# SECUREBRD_001.net
KiCad netlist of a schematic drawn in EAGLE
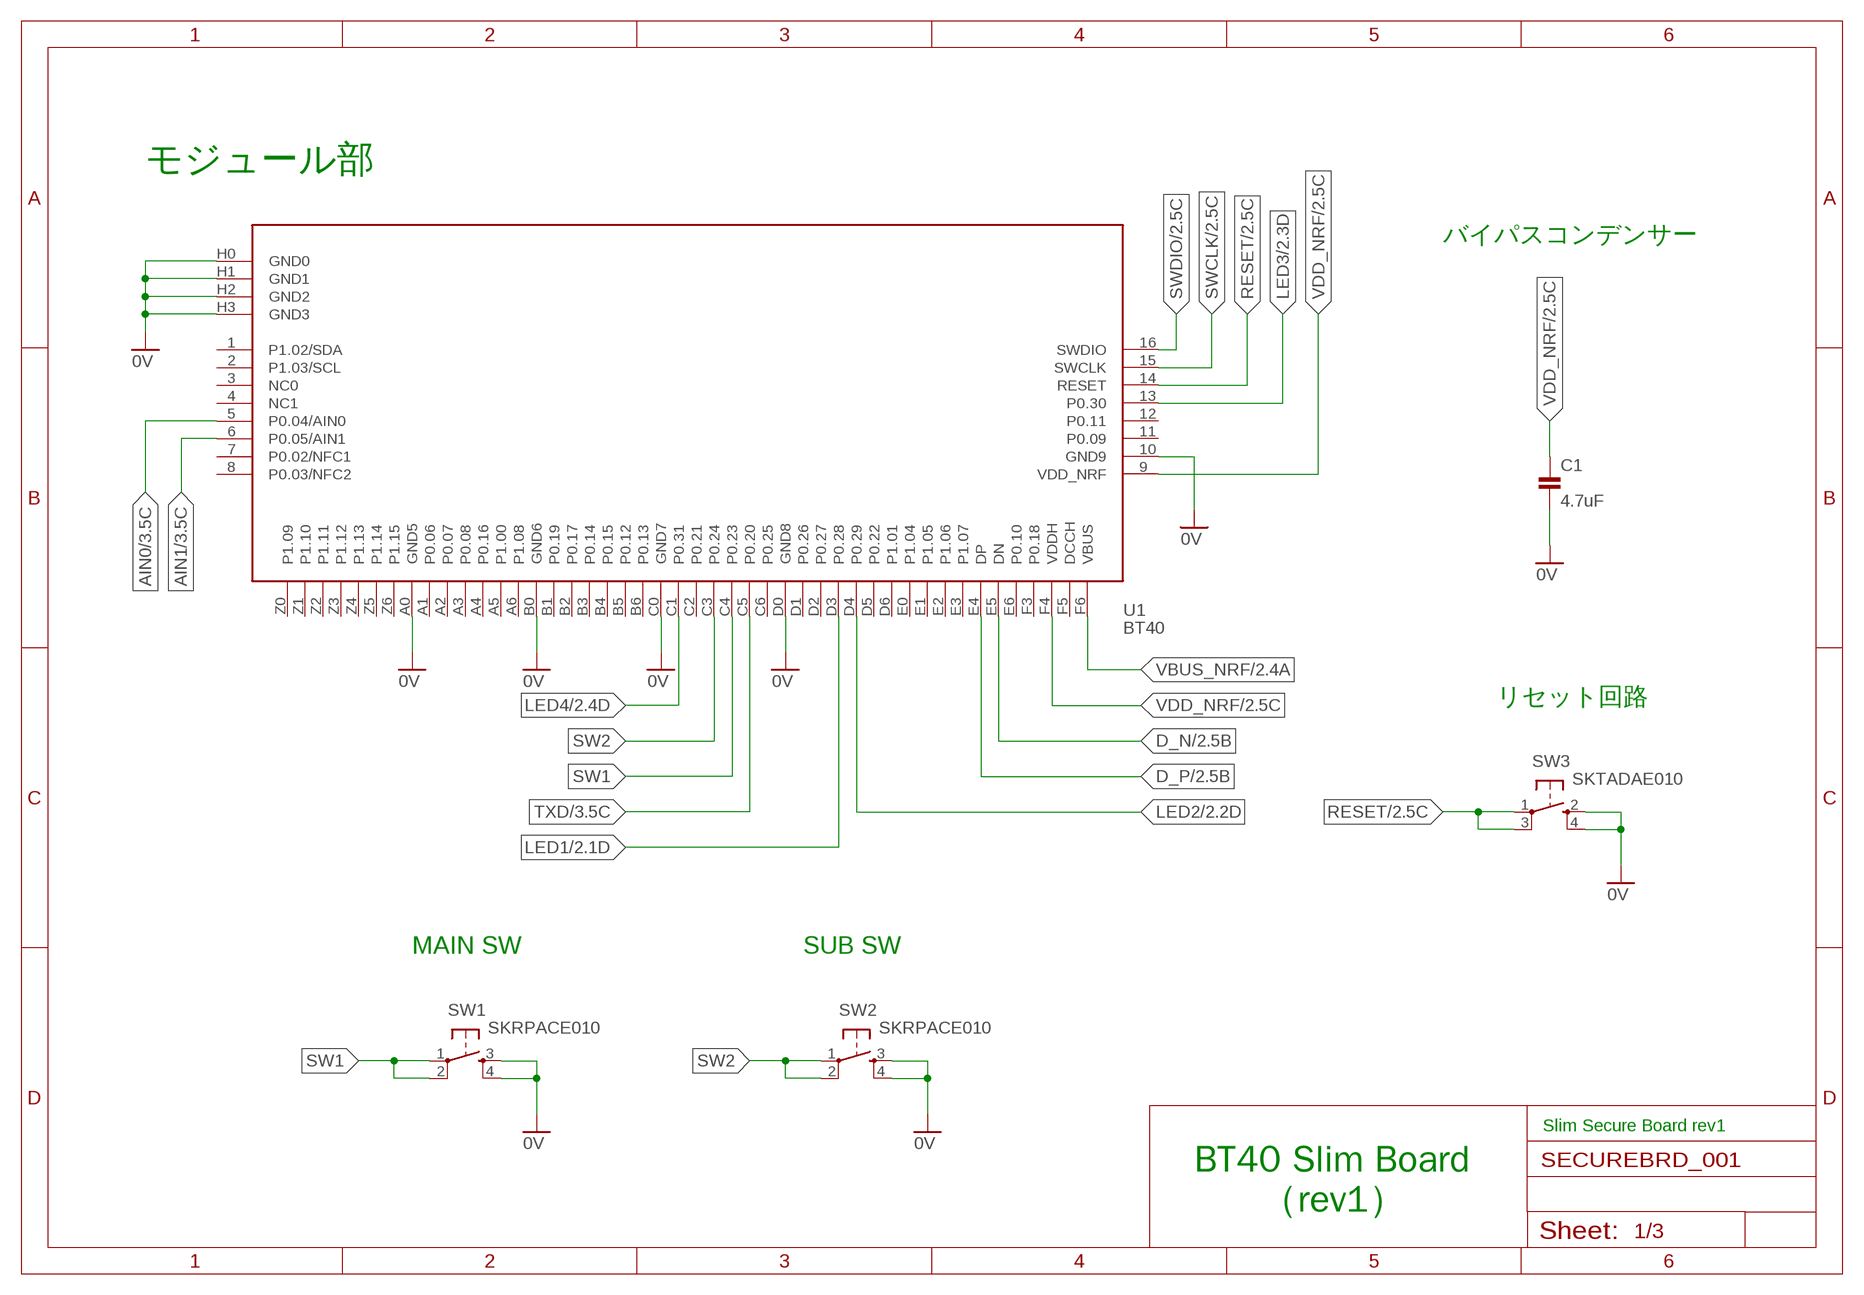
[diagram p0: schematic, sheet 1]
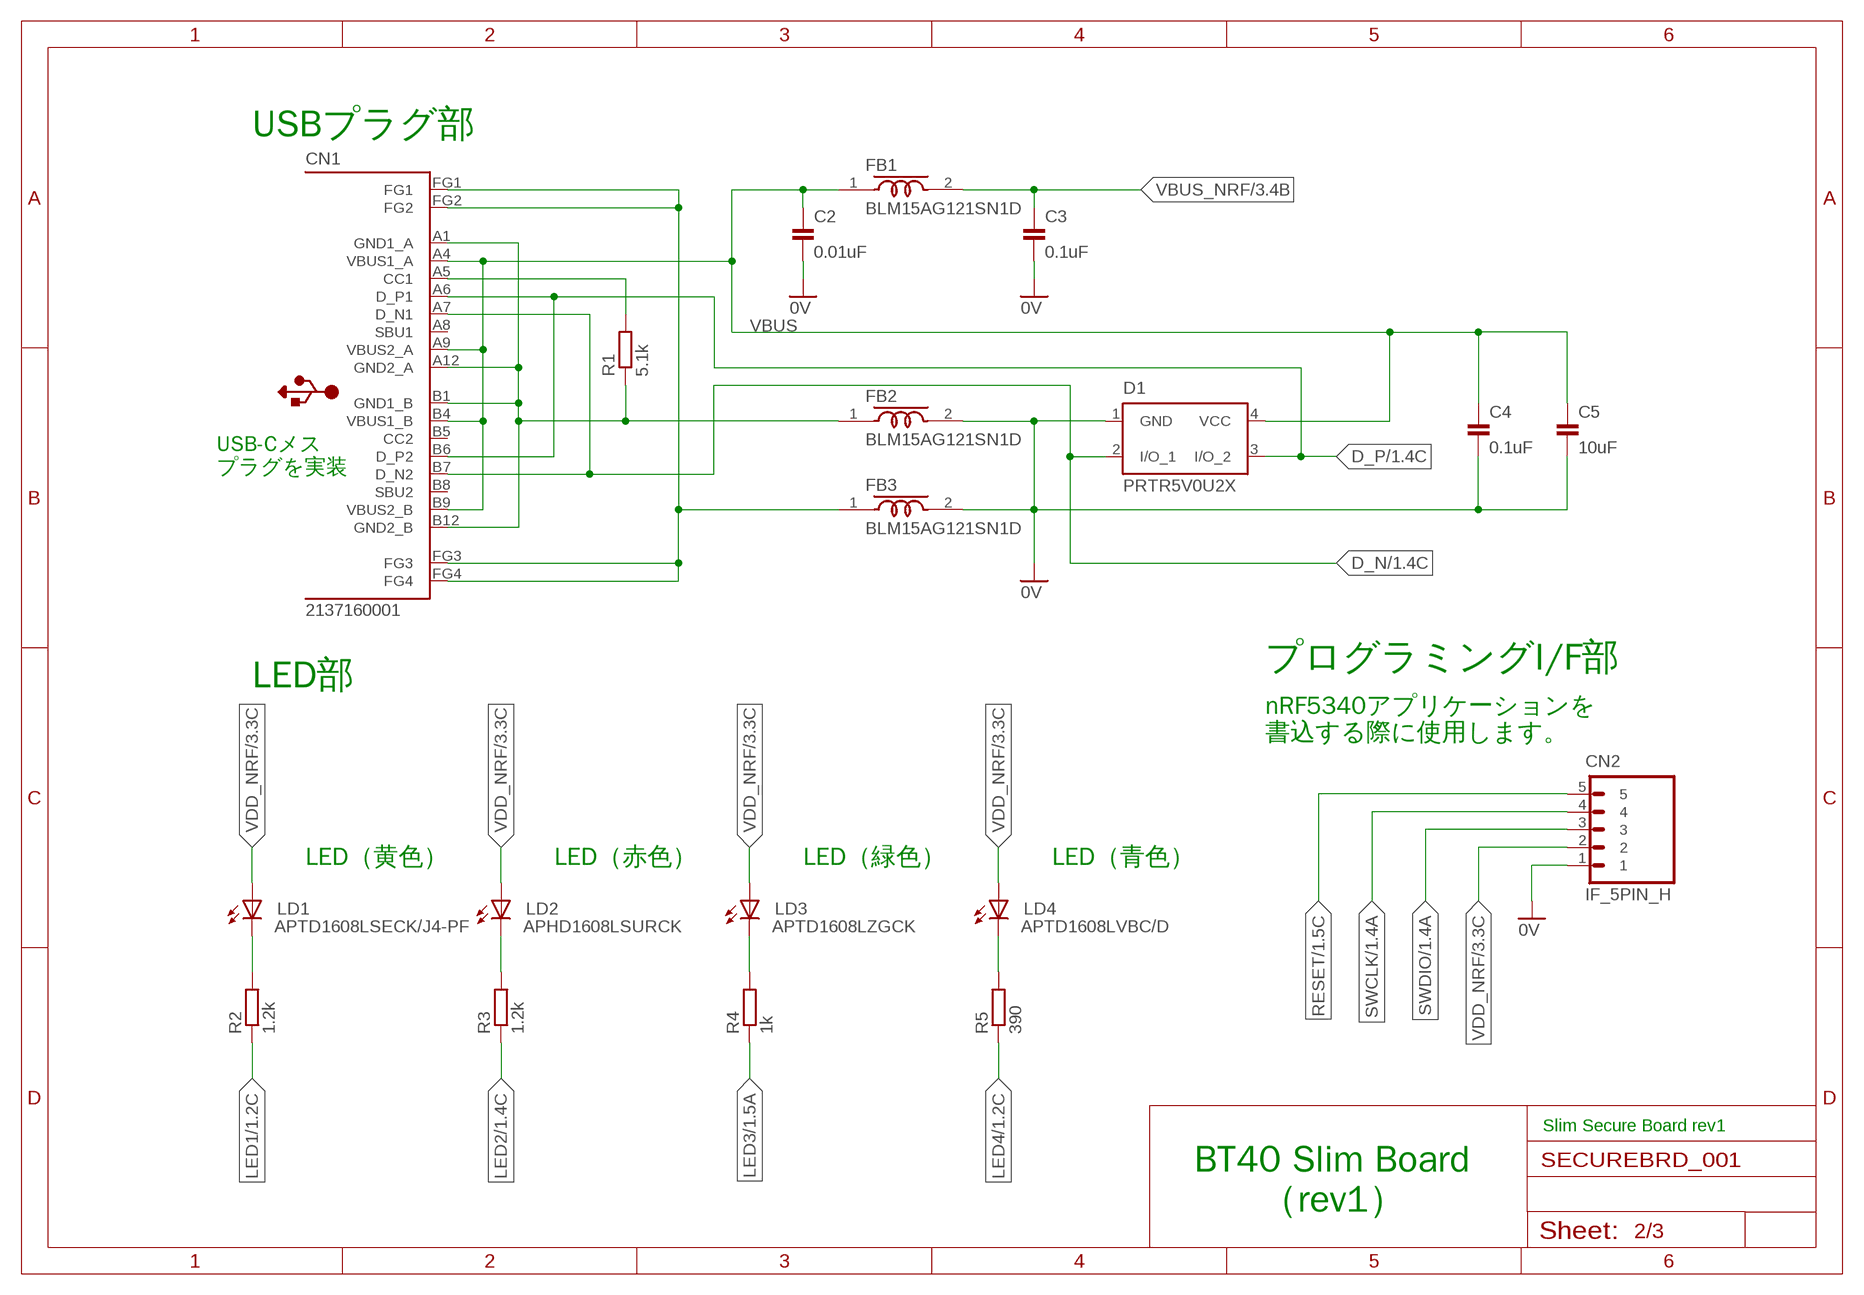
[diagram p1: schematic, sheet 2]
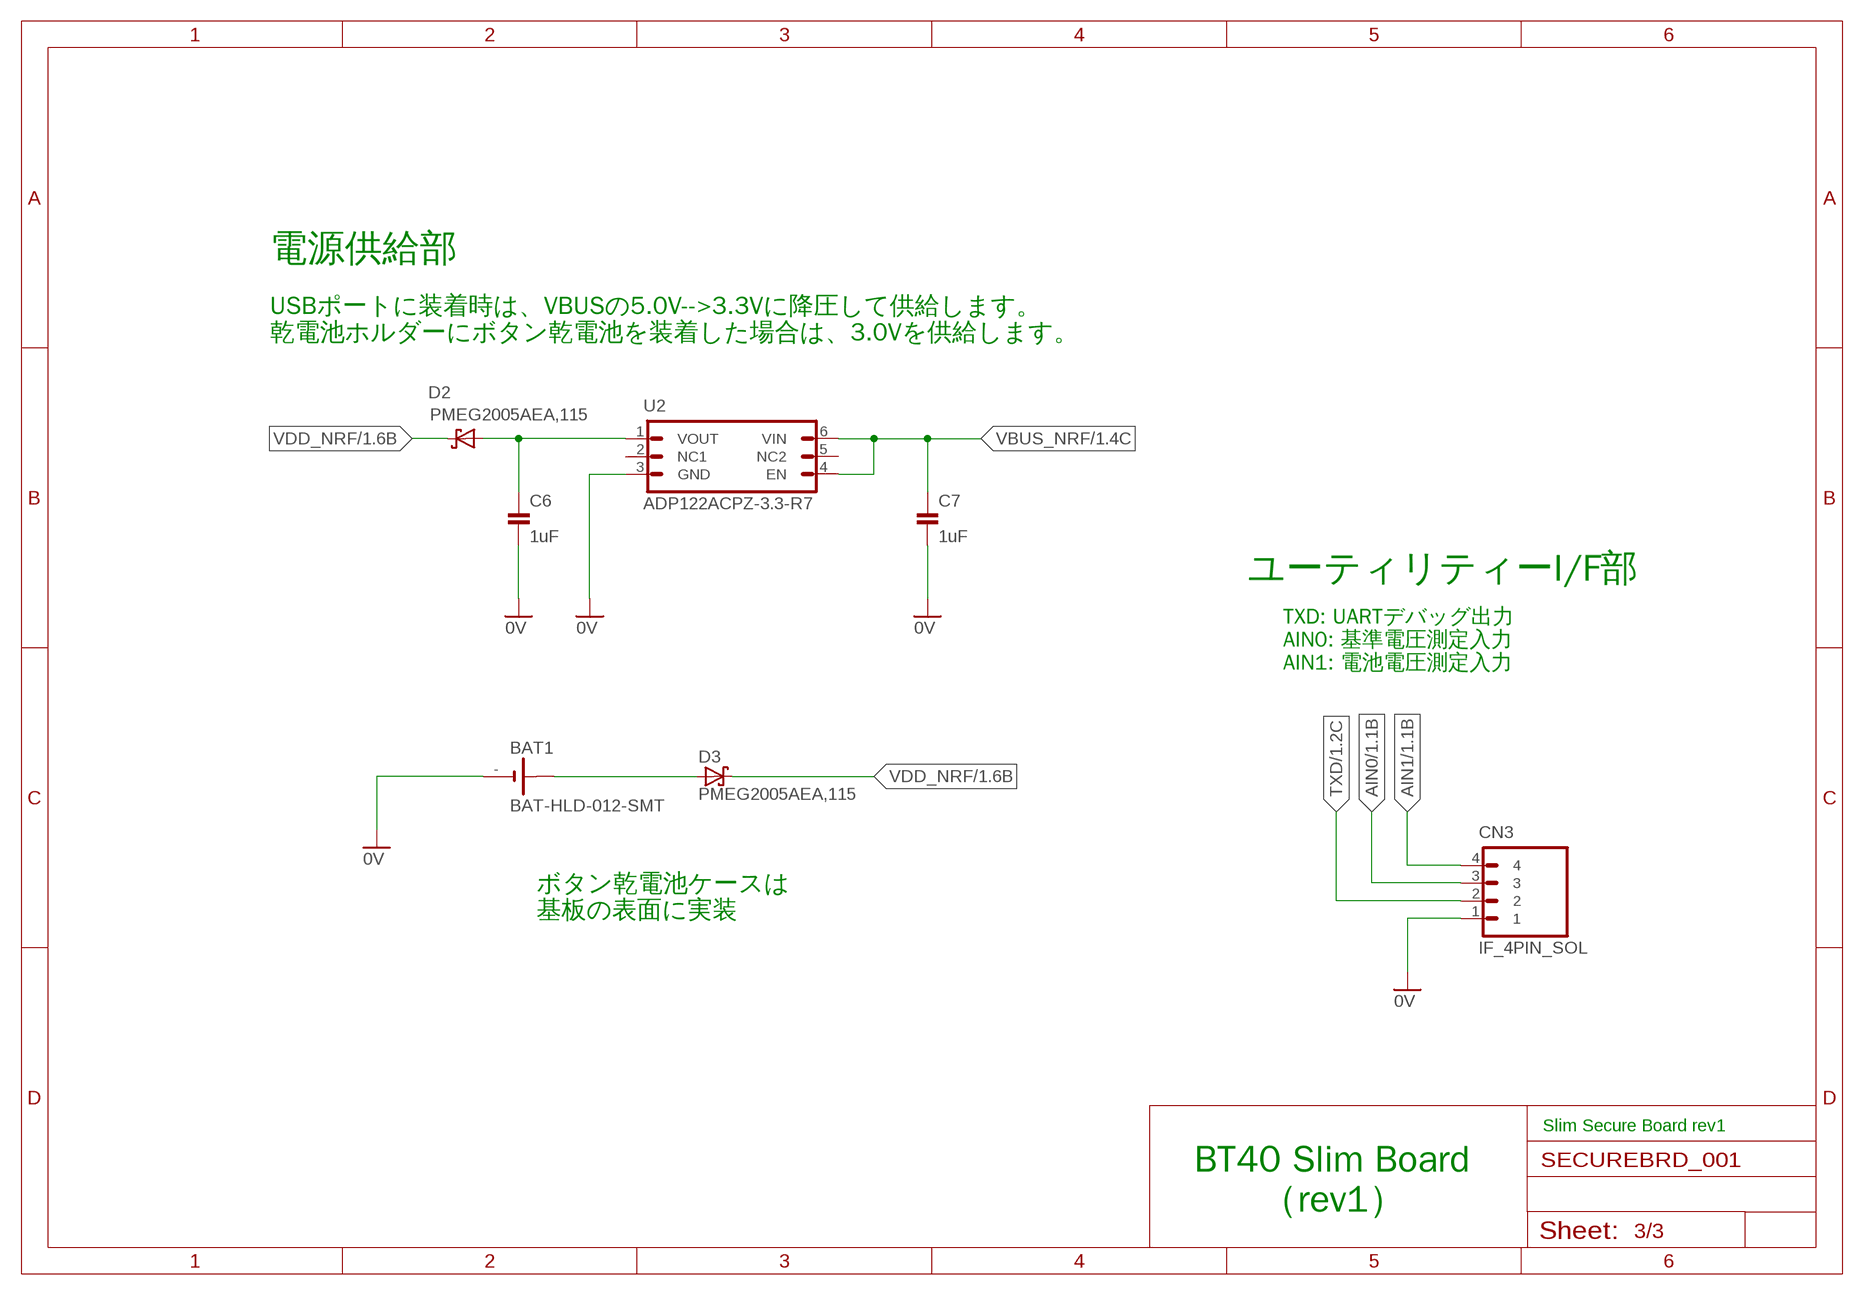
[diagram p2: schematic, sheet 3]

(export (version "E")
  (design (tool "Eeschema 10.0.6"))
  (components
    (comp (ref "C1")
      (value "4.7uF")
      (footprint "eagle-import:C0603K")
      (libsource (lib "eagle-import") (part "CAP_0603"))
    )
    (comp (ref "SW1")
      (value "SKRPACE010")
      (footprint "eagle-import:SKRPACE010")
      (libsource (lib "eagle-import") (part "SKRPACE010"))
    )
    (comp (ref "SW2")
      (value "SKRPACE010")
      (footprint "eagle-import:SKRPACE010")
      (libsource (lib "eagle-import") (part "SKRPACE010"))
    )
    (comp (ref "SW3")
      (value "SKTADAE010")
      (footprint "eagle-import:SKTADAE010")
      (libsource (lib "eagle-import") (part "SKTADAE010"))
    )
    (comp (ref "U1")
      (value "BT40")
      (footprint "eagle-import:BM40-B_1PRIMARY")
      (libsource (lib "eagle-import") (part "BT40"))
    )
    (comp (ref "BAT1")
      (value "BAT-HLD-012-SMT")
      (footprint "eagle-import:BAT-HLD-012-SMT")
      (libsource (lib "eagle-import") (part "BAT-HLD-012-SMT"))
    )
    (comp (ref "C6")
      (value "1uF")
      (footprint "eagle-import:C0603K")
      (libsource (lib "eagle-import") (part "CAP_0603"))
    )
    (comp (ref "C7")
      (value "1uF")
      (footprint "eagle-import:C0603K")
      (libsource (lib "eagle-import") (part "CAP_0603"))
    )
    (comp (ref "CN3")
      (value "IF_4PIN_SOL")
      (footprint "eagle-import:SOLPAD_4PIN")
      (libsource (lib "eagle-import") (part "IF_4PIN_SOL"))
    )
    (comp (ref "D2")
      (value "PMEG2005AEA,115")
      (footprint "eagle-import:SOD323-W")
      (libsource (lib "eagle-import") (part "PMEG2005AEA,115"))
    )
    (comp (ref "D3")
      (value "PMEG2005AEA,115")
      (footprint "eagle-import:SOD323-W")
      (libsource (lib "eagle-import") (part "PMEG2005AEA,115"))
    )
    (comp (ref "U2")
      (value "ADP122ACPZ-3.3-R7")
      (footprint "eagle-import:6-LFCSP_UD")
      (libsource (lib "eagle-import") (part "ADP122ACPZ-3.3-R7"))
    )
    (comp (ref "C2")
      (value "0.01uF")
      (footprint "eagle-import:C0402K")
      (libsource (lib "eagle-import") (part "CAP_0402K"))
    )
    (comp (ref "C3")
      (value "0.1uF")
      (footprint "eagle-import:C0402K")
      (libsource (lib "eagle-import") (part "CAP_0402K"))
    )
    (comp (ref "C4")
      (value "0.1uF")
      (footprint "eagle-import:C0402K")
      (libsource (lib "eagle-import") (part "CAP_0402K"))
    )
    (comp (ref "C5")
      (value "10uF")
      (footprint "eagle-import:C0603K")
      (libsource (lib "eagle-import") (part "CAP_0603"))
    )
    (comp (ref "CN1")
      (value "2137160001")
      (footprint "eagle-import:2137160001")
      (libsource (lib "eagle-import") (part "2137160001"))
    )
    (comp (ref "CN2")
      (value "IF_5PIN_H")
      (footprint "eagle-import:HEADER_5PIN")
      (libsource (lib "eagle-import") (part "IF_5PIN_H"))
    )
    (comp (ref "D1")
      (value "PRTR5V0U2X")
      (footprint "eagle-import:SOT143B")
      (libsource (lib "eagle-import") (part "PRTR5V0U2X"))
    )
    (comp (ref "FB1")
      (value "BLM15AG121SN1D")
      (footprint "eagle-import:C0402K")
      (libsource (lib "eagle-import") (part "BLM15AG121SN1D"))
    )
    (comp (ref "FB2")
      (value "BLM15AG121SN1D")
      (footprint "eagle-import:C0402K")
      (libsource (lib "eagle-import") (part "BLM15AG121SN1D"))
    )
    (comp (ref "FB3")
      (value "BLM15AG121SN1D")
      (footprint "eagle-import:C0402K")
      (libsource (lib "eagle-import") (part "BLM15AG121SN1D"))
    )
    (comp (ref "LD1")
      (value "APTD1608LSECK/J4-PF")
      (footprint "eagle-import:APTD1608")
      (libsource (lib "eagle-import") (part "APTD1608LSECK/J4-PF"))
    )
    (comp (ref "LD2")
      (value "APHD1608LSURCK")
      (footprint "eagle-import:APTD1608")
      (libsource (lib "eagle-import") (part "APHD1608LSURCK"))
    )
    (comp (ref "LD3")
      (value "APTD1608LZGCK")
      (footprint "eagle-import:APTD1608")
      (libsource (lib "eagle-import") (part "APTD1608LZGCK"))
    )
    (comp (ref "LD4")
      (value "APTD1608LVBC/D")
      (footprint "eagle-import:APTD1608")
      (libsource (lib "eagle-import") (part "APTD1608LVBC/D"))
    )
    (comp (ref "R1")
      (value "5.1k")
      (footprint "eagle-import:R0402")
      (libsource (lib "eagle-import") (part "RESISTOR_0402"))
    )
    (comp (ref "R2")
      (value "1.2k")
      (footprint "eagle-import:R0402")
      (libsource (lib "eagle-import") (part "RESISTOR_0402"))
    )
    (comp (ref "R3")
      (value "1.2k")
      (footprint "eagle-import:R0402")
      (libsource (lib "eagle-import") (part "RESISTOR_0402"))
    )
    (comp (ref "R4")
      (value "1k")
      (footprint "eagle-import:R0402")
      (libsource (lib "eagle-import") (part "RESISTOR_0402"))
    )
    (comp (ref "R5")
      (value "390")
      (footprint "eagle-import:R0402")
      (libsource (lib "eagle-import") (part "RESISTOR_0402"))
    )
  )
  (nets
    (net (code "1") (name "0V") (class "Default")
      (node (ref "BAT1") (pin "-") (pinfunction "-_-") (pintype "passive"))
      (node (ref "C1") (pin "2") (pinfunction "2_2") (pintype "passive"))
      (node (ref "C2") (pin "2") (pinfunction "2_2") (pintype "passive"))
      (node (ref "C3") (pin "2") (pinfunction "2_2") (pintype "passive"))
      (node (ref "C4") (pin "2") (pinfunction "2_2") (pintype "passive"))
      (node (ref "C5") (pin "2") (pinfunction "2_2") (pintype "passive"))
      (node (ref "C6") (pin "2") (pinfunction "2_2") (pintype "passive"))
      (node (ref "C7") (pin "2") (pinfunction "2_2") (pintype "passive"))
      (node (ref "CN2") (pin "1") (pinfunction "1_1") (pintype "passive"))
      (node (ref "CN3") (pin "1") (pinfunction "1_1") (pintype "passive"))
      (node (ref "D1") (pin "1") (pinfunction "GND_1") (pintype "passive"))
      (node (ref "FB2") (pin "2") (pinfunction "2_2") (pintype "passive"))
      (node (ref "FB3") (pin "2") (pinfunction "2_2") (pintype "passive"))
      (node (ref "SW1") (pin "3") (pinfunction "S_3") (pintype "passive"))
      (node (ref "SW1") (pin "4") (pinfunction "S1_4") (pintype "passive"))
      (node (ref "SW2") (pin "3") (pinfunction "S_3") (pintype "passive"))
      (node (ref "SW2") (pin "4") (pinfunction "S1_4") (pintype "passive"))
      (node (ref "SW3") (pin "2") (pinfunction "S_2") (pintype "passive"))
      (node (ref "SW3") (pin "4") (pinfunction "S1_4") (pintype "passive"))
      (node (ref "U1") (pin "10") (pinfunction "GND9_10") (pintype "passive"))
      (node (ref "U1") (pin "A0") (pinfunction "GND5_A0") (pintype "passive"))
      (node (ref "U1") (pin "B0") (pinfunction "GND6_B0") (pintype "passive"))
      (node (ref "U1") (pin "C0") (pinfunction "GND7_C0") (pintype "passive"))
      (node (ref "U1") (pin "D0") (pinfunction "GND8_D0") (pintype "passive"))
      (node (ref "U1") (pin "H0") (pinfunction "GND0_H0") (pintype "passive"))
      (node (ref "U1") (pin "H1") (pinfunction "GND1_H1") (pintype "passive"))
      (node (ref "U1") (pin "H2") (pinfunction "GND2_H2") (pintype "passive"))
      (node (ref "U1") (pin "H3") (pinfunction "GND3_H3") (pintype "passive"))
      (node (ref "U2") (pin "3") (pinfunction "GND_3") (pintype "passive"))
    )
    (net (code "2") (name "AIN0") (class "Default")
      (node (ref "CN3") (pin "3") (pinfunction "3_3") (pintype "passive"))
      (node (ref "U1") (pin "5") (pinfunction "P0.04/AIN0_5") (pintype "bidirectional"))
    )
    (net (code "3") (name "AIN1") (class "Default")
      (node (ref "CN3") (pin "4") (pinfunction "4_4") (pintype "passive"))
      (node (ref "U1") (pin "6") (pinfunction "P0.05/AIN1_6") (pintype "bidirectional"))
    )
    (net (code "4") (name "D_N") (class "Default")
      (node (ref "CN1") (pin "A7") (pinfunction "D_N1_A7") (pintype "bidirectional"))
      (node (ref "CN1") (pin "B7") (pinfunction "D_N2_B7") (pintype "bidirectional"))
      (node (ref "D1") (pin "2") (pinfunction "I/O_1_2") (pintype "bidirectional"))
      (node (ref "U1") (pin "E5") (pinfunction "DN_E5") (pintype "bidirectional"))
    )
    (net (code "5") (name "D_P") (class "Default")
      (node (ref "CN1") (pin "A6") (pinfunction "D_P1_A6") (pintype "bidirectional"))
      (node (ref "CN1") (pin "B6") (pinfunction "D_P2_B6") (pintype "bidirectional"))
      (node (ref "D1") (pin "3") (pinfunction "I/O_2_3") (pintype "bidirectional"))
      (node (ref "U1") (pin "E4") (pinfunction "DP_E4") (pintype "bidirectional"))
    )
    (net (code "6") (name "LED1") (class "Default")
      (node (ref "R2") (pin "1") (pinfunction "1_1") (pintype "passive"))
      (node (ref "U1") (pin "D3") (pinfunction "P0.28_D3") (pintype "bidirectional"))
    )
    (net (code "7") (name "LED2") (class "Default")
      (node (ref "R3") (pin "1") (pinfunction "1_1") (pintype "passive"))
      (node (ref "U1") (pin "D4") (pinfunction "P0.29_D4") (pintype "bidirectional"))
    )
    (net (code "8") (name "LED3") (class "Default")
      (node (ref "R4") (pin "1") (pinfunction "1_1") (pintype "passive"))
      (node (ref "U1") (pin "13") (pinfunction "P0.30_13") (pintype "bidirectional"))
    )
    (net (code "9") (name "LED4") (class "Default")
      (node (ref "R5") (pin "1") (pinfunction "1_1") (pintype "passive"))
      (node (ref "U1") (pin "C1") (pinfunction "P0.31_C1") (pintype "bidirectional"))
    )
    (net (code "10") (name "Net-(BAT1-+)") (class "Default")
      (node (ref "BAT1") (pin "+@2") (pinfunction "+_+@2") (pintype "passive"))
      (node (ref "D3") (pin "A") (pinfunction "A_A") (pintype "passive"))
    )
    (net (code "11") (name "Net-(CN1-CC1)") (class "Default")
      (node (ref "CN1") (pin "A5") (pinfunction "CC1_A5") (pintype "passive"))
      (node (ref "R1") (pin "2") (pinfunction "2_2") (pintype "passive"))
    )
    (net (code "12") (name "Net-(CN1-GND1_A)") (class "Default")
      (node (ref "CN1") (pin "A1") (pinfunction "GND1_A_A1") (pintype "passive"))
      (node (ref "CN1") (pin "A12") (pinfunction "GND2_A_A12") (pintype "passive"))
      (node (ref "CN1") (pin "B1") (pinfunction "GND1_B_B1") (pintype "passive"))
      (node (ref "CN1") (pin "B12") (pinfunction "GND2_B_B12") (pintype "passive"))
      (node (ref "FB2") (pin "1") (pinfunction "1_1") (pintype "passive"))
      (node (ref "R1") (pin "1") (pinfunction "1_1") (pintype "passive"))
    )
    (net (code "13") (name "Net-(CN1-PadFG1)") (class "Default")
      (node (ref "CN1") (pin "FG1") (pinfunction "FG1_FG1") (pintype "passive"))
      (node (ref "CN1") (pin "FG2") (pinfunction "FG2_FG2") (pintype "bidirectional"))
      (node (ref "CN1") (pin "FG3") (pinfunction "FG3_FG3") (pintype "passive"))
      (node (ref "CN1") (pin "FG4") (pinfunction "FG4_FG4") (pintype "passive"))
      (node (ref "FB3") (pin "1") (pinfunction "1_1") (pintype "passive"))
    )
    (net (code "14") (name "Net-(LD1-PadC)") (class "Default")
      (node (ref "LD1") (pin "C") (pinfunction "C_C") (pintype "passive"))
      (node (ref "R2") (pin "2") (pinfunction "2_2") (pintype "passive"))
    )
    (net (code "15") (name "Net-(LD2-PadC)") (class "Default")
      (node (ref "LD2") (pin "C") (pinfunction "C_C") (pintype "passive"))
      (node (ref "R3") (pin "2") (pinfunction "2_2") (pintype "passive"))
    )
    (net (code "16") (name "Net-(LD3-PadC)") (class "Default")
      (node (ref "LD3") (pin "C") (pinfunction "C_C") (pintype "passive"))
      (node (ref "R4") (pin "2") (pinfunction "2_2") (pintype "passive"))
    )
    (net (code "17") (name "Net-(LD4-PadC)") (class "Default")
      (node (ref "LD4") (pin "C") (pinfunction "C_C") (pintype "passive"))
      (node (ref "R5") (pin "2") (pinfunction "2_2") (pintype "passive"))
    )
    (net (code "18") (name "Net-(U2-VOUT)") (class "Default")
      (node (ref "C6") (pin "1") (pinfunction "1_1") (pintype "passive"))
      (node (ref "D2") (pin "A") (pinfunction "A_A") (pintype "passive"))
      (node (ref "U2") (pin "1") (pinfunction "VOUT_1") (pintype "passive"))
    )
    (net (code "19") (name "RESET") (class "Default")
      (node (ref "CN2") (pin "5") (pinfunction "5_5") (pintype "passive"))
      (node (ref "SW3") (pin "1") (pinfunction "P_1") (pintype "passive"))
      (node (ref "SW3") (pin "3") (pinfunction "P1_3") (pintype "passive"))
      (node (ref "U1") (pin "14") (pinfunction "RESET_14") (pintype "bidirectional"))
    )
    (net (code "20") (name "SW1") (class "Default")
      (node (ref "SW1") (pin "1") (pinfunction "P_1") (pintype "passive"))
      (node (ref "SW1") (pin "2") (pinfunction "P1_2") (pintype "passive"))
      (node (ref "U1") (pin "C4") (pinfunction "P0.23_C4") (pintype "bidirectional"))
    )
    (net (code "21") (name "SW2") (class "Default")
      (node (ref "SW2") (pin "1") (pinfunction "P_1") (pintype "passive"))
      (node (ref "SW2") (pin "2") (pinfunction "P1_2") (pintype "passive"))
      (node (ref "U1") (pin "C3") (pinfunction "P0.24_C3") (pintype "bidirectional"))
    )
    (net (code "22") (name "SWCLK") (class "Default")
      (node (ref "CN2") (pin "4") (pinfunction "4_4") (pintype "passive"))
      (node (ref "U1") (pin "15") (pinfunction "SWCLK_15") (pintype "bidirectional"))
    )
    (net (code "23") (name "SWDIO") (class "Default")
      (node (ref "CN2") (pin "3") (pinfunction "3_3") (pintype "passive"))
      (node (ref "U1") (pin "16") (pinfunction "SWDIO_16") (pintype "bidirectional"))
    )
    (net (code "24") (name "TXD") (class "Default")
      (node (ref "CN3") (pin "2") (pinfunction "2_2") (pintype "passive"))
      (node (ref "U1") (pin "C5") (pinfunction "P0.20_C5") (pintype "bidirectional"))
    )
    (net (code "25") (name "VBUS") (class "Default")
      (node (ref "C2") (pin "1") (pinfunction "1_1") (pintype "passive"))
      (node (ref "C4") (pin "1") (pinfunction "1_1") (pintype "passive"))
      (node (ref "C5") (pin "1") (pinfunction "1_1") (pintype "passive"))
      (node (ref "CN1") (pin "A4") (pinfunction "VBUS1_A_A4") (pintype "passive"))
      (node (ref "CN1") (pin "A9") (pinfunction "VBUS2_A_A9") (pintype "passive"))
      (node (ref "CN1") (pin "B4") (pinfunction "VBUS1_B_B4") (pintype "passive"))
      (node (ref "CN1") (pin "B9") (pinfunction "VBUS2_B_B9") (pintype "passive"))
      (node (ref "D1") (pin "4") (pinfunction "VCC_4") (pintype "passive"))
      (node (ref "FB1") (pin "1") (pinfunction "1_1") (pintype "passive"))
    )
    (net (code "26") (name "VBUS_NRF") (class "Default")
      (node (ref "C3") (pin "1") (pinfunction "1_1") (pintype "passive"))
      (node (ref "C7") (pin "1") (pinfunction "1_1") (pintype "passive"))
      (node (ref "FB1") (pin "2") (pinfunction "2_2") (pintype "passive"))
      (node (ref "U1") (pin "F6") (pinfunction "VBUS_F6") (pintype "passive"))
      (node (ref "U2") (pin "4") (pinfunction "EN_4") (pintype "bidirectional"))
      (node (ref "U2") (pin "6") (pinfunction "VIN_6") (pintype "passive"))
    )
    (net (code "27") (name "VDD_NRF") (class "Default")
      (node (ref "C1") (pin "1") (pinfunction "1_1") (pintype "passive"))
      (node (ref "CN2") (pin "2") (pinfunction "2_2") (pintype "passive"))
      (node (ref "D2") (pin "C") (pinfunction "C_C") (pintype "passive"))
      (node (ref "D3") (pin "C") (pinfunction "C_C") (pintype "passive"))
      (node (ref "LD1") (pin "A") (pinfunction "A_A") (pintype "passive"))
      (node (ref "LD2") (pin "A") (pinfunction "A_A") (pintype "passive"))
      (node (ref "LD3") (pin "A") (pinfunction "A_A") (pintype "passive"))
      (node (ref "LD4") (pin "A") (pinfunction "A_A") (pintype "passive"))
      (node (ref "U1") (pin "9") (pinfunction "VDD_NRF_9") (pintype "passive"))
      (node (ref "U1") (pin "F4") (pinfunction "VDDH_F4") (pintype "passive"))
    )
    (net (code "28") (name "unconnected-(CN1-CC2-PadB5)") (class "Default")
      (node (ref "CN1") (pin "B5") (pinfunction "CC2_B5") (pintype "passive"))
    )
    (net (code "29") (name "unconnected-(CN1-SBU1-PadA8)") (class "Default")
      (node (ref "CN1") (pin "A8") (pinfunction "SBU1_A8") (pintype "passive"))
    )
    (net (code "30") (name "unconnected-(CN1-SBU2-PadB8)") (class "Default")
      (node (ref "CN1") (pin "B8") (pinfunction "SBU2_B8") (pintype "passive"))
    )
    (net (code "31") (name "unconnected-(U1-DCCH-PadF5)") (class "Default")
      (node (ref "U1") (pin "F5") (pinfunction "DCCH_F5") (pintype "passive"))
    )
    (net (code "32") (name "unconnected-(U1-NC0-Pad3)") (class "Default")
      (node (ref "U1") (pin "3") (pinfunction "NC0_3") (pintype "no_connect"))
    )
    (net (code "33") (name "unconnected-(U1-NC1-Pad4)") (class "Default")
      (node (ref "U1") (pin "4") (pinfunction "NC1_4") (pintype "no_connect"))
    )
    (net (code "34") (name "unconnected-(U1-P0.02{slash}NFC1-Pad7)") (class "Default")
      (node (ref "U1") (pin "7") (pinfunction "P0.02/NFC1_7") (pintype "bidirectional"))
    )
    (net (code "35") (name "unconnected-(U1-P0.03{slash}NFC2-Pad8)") (class "Default")
      (node (ref "U1") (pin "8") (pinfunction "P0.03/NFC2_8") (pintype "bidirectional"))
    )
    (net (code "36") (name "unconnected-(U1-P0.06-PadA1)") (class "Default")
      (node (ref "U1") (pin "A1") (pinfunction "P0.06_A1") (pintype "bidirectional"))
    )
    (net (code "37") (name "unconnected-(U1-P0.07-PadA2)") (class "Default")
      (node (ref "U1") (pin "A2") (pinfunction "P0.07_A2") (pintype "bidirectional"))
    )
    (net (code "38") (name "unconnected-(U1-P0.08-PadA3)") (class "Default")
      (node (ref "U1") (pin "A3") (pinfunction "P0.08_A3") (pintype "bidirectional"))
    )
    (net (code "39") (name "unconnected-(U1-P0.09-Pad11)") (class "Default")
      (node (ref "U1") (pin "11") (pinfunction "P0.09_11") (pintype "bidirectional"))
    )
    (net (code "40") (name "unconnected-(U1-P0.10-PadE6)") (class "Default")
      (node (ref "U1") (pin "E6") (pinfunction "P0.10_E6") (pintype "bidirectional"))
    )
    (net (code "41") (name "unconnected-(U1-P0.11-Pad12)") (class "Default")
      (node (ref "U1") (pin "12") (pinfunction "P0.11_12") (pintype "bidirectional"))
    )
    (net (code "42") (name "unconnected-(U1-P0.12-PadB5)") (class "Default")
      (node (ref "U1") (pin "B5") (pinfunction "P0.12_B5") (pintype "bidirectional"))
    )
    (net (code "43") (name "unconnected-(U1-P0.13-PadB6)") (class "Default")
      (node (ref "U1") (pin "B6") (pinfunction "P0.13_B6") (pintype "bidirectional"))
    )
    (net (code "44") (name "unconnected-(U1-P0.14-PadB3)") (class "Default")
      (node (ref "U1") (pin "B3") (pinfunction "P0.14_B3") (pintype "bidirectional"))
    )
    (net (code "45") (name "unconnected-(U1-P0.15-PadB4)") (class "Default")
      (node (ref "U1") (pin "B4") (pinfunction "P0.15_B4") (pintype "bidirectional"))
    )
    (net (code "46") (name "unconnected-(U1-P0.16-PadA4)") (class "Default")
      (node (ref "U1") (pin "A4") (pinfunction "P0.16_A4") (pintype "bidirectional"))
    )
    (net (code "47") (name "unconnected-(U1-P0.17-PadB2)") (class "Default")
      (node (ref "U1") (pin "B2") (pinfunction "P0.17_B2") (pintype "bidirectional"))
    )
    (net (code "48") (name "unconnected-(U1-P0.18-PadF3)") (class "Default")
      (node (ref "U1") (pin "F3") (pinfunction "P0.18_F3") (pintype "bidirectional"))
    )
    (net (code "49") (name "unconnected-(U1-P0.19-PadB1)") (class "Default")
      (node (ref "U1") (pin "B1") (pinfunction "P0.19_B1") (pintype "bidirectional"))
    )
    (net (code "50") (name "unconnected-(U1-P0.21-PadC2)") (class "Default")
      (node (ref "U1") (pin "C2") (pinfunction "P0.21_C2") (pintype "bidirectional"))
    )
    (net (code "51") (name "unconnected-(U1-P0.22-PadD5)") (class "Default")
      (node (ref "U1") (pin "D5") (pinfunction "P0.22_D5") (pintype "bidirectional"))
    )
    (net (code "52") (name "unconnected-(U1-P0.25-PadC6)") (class "Default")
      (node (ref "U1") (pin "C6") (pinfunction "P0.25_C6") (pintype "bidirectional"))
    )
    (net (code "53") (name "unconnected-(U1-P0.26-PadD1)") (class "Default")
      (node (ref "U1") (pin "D1") (pinfunction "P0.26_D1") (pintype "bidirectional"))
    )
    (net (code "54") (name "unconnected-(U1-P0.27-PadD2)") (class "Default")
      (node (ref "U1") (pin "D2") (pinfunction "P0.27_D2") (pintype "bidirectional"))
    )
    (net (code "55") (name "unconnected-(U1-P1.00-PadA5)") (class "Default")
      (node (ref "U1") (pin "A5") (pinfunction "P1.00_A5") (pintype "bidirectional"))
    )
    (net (code "56") (name "unconnected-(U1-P1.01-PadD6)") (class "Default")
      (node (ref "U1") (pin "D6") (pinfunction "P1.01_D6") (pintype "bidirectional"))
    )
    (net (code "57") (name "unconnected-(U1-P1.02{slash}SDA-Pad1)") (class "Default")
      (node (ref "U1") (pin "1") (pinfunction "P1.02/SDA_1") (pintype "bidirectional"))
    )
    (net (code "58") (name "unconnected-(U1-P1.03{slash}SCL-Pad2)") (class "Default")
      (node (ref "U1") (pin "2") (pinfunction "P1.03/SCL_2") (pintype "bidirectional"))
    )
    (net (code "59") (name "unconnected-(U1-P1.04-PadE0)") (class "Default")
      (node (ref "U1") (pin "E0") (pinfunction "P1.04_E0") (pintype "bidirectional"))
    )
    (net (code "60") (name "unconnected-(U1-P1.05-PadE1)") (class "Default")
      (node (ref "U1") (pin "E1") (pinfunction "P1.05_E1") (pintype "bidirectional"))
    )
    (net (code "61") (name "unconnected-(U1-P1.06-PadE2)") (class "Default")
      (node (ref "U1") (pin "E2") (pinfunction "P1.06_E2") (pintype "bidirectional"))
    )
    (net (code "62") (name "unconnected-(U1-P1.07-PadE3)") (class "Default")
      (node (ref "U1") (pin "E3") (pinfunction "P1.07_E3") (pintype "bidirectional"))
    )
    (net (code "63") (name "unconnected-(U1-P1.08-PadA6)") (class "Default")
      (node (ref "U1") (pin "A6") (pinfunction "P1.08_A6") (pintype "bidirectional"))
    )
    (net (code "64") (name "unconnected-(U1-P1.09-PadZ0)") (class "Default")
      (node (ref "U1") (pin "Z0") (pinfunction "P1.09_Z0") (pintype "bidirectional"))
    )
    (net (code "65") (name "unconnected-(U1-P1.10-PadZ1)") (class "Default")
      (node (ref "U1") (pin "Z1") (pinfunction "P1.10_Z1") (pintype "bidirectional"))
    )
    (net (code "66") (name "unconnected-(U1-P1.11-PadZ2)") (class "Default")
      (node (ref "U1") (pin "Z2") (pinfunction "P1.11_Z2") (pintype "bidirectional"))
    )
    (net (code "67") (name "unconnected-(U1-P1.12-PadZ3)") (class "Default")
      (node (ref "U1") (pin "Z3") (pinfunction "P1.12_Z3") (pintype "bidirectional"))
    )
    (net (code "68") (name "unconnected-(U1-P1.13-PadZ4)") (class "Default")
      (node (ref "U1") (pin "Z4") (pinfunction "P1.13_Z4") (pintype "bidirectional"))
    )
    (net (code "69") (name "unconnected-(U1-P1.14-PadZ5)") (class "Default")
      (node (ref "U1") (pin "Z5") (pinfunction "P1.14_Z5") (pintype "bidirectional"))
    )
    (net (code "70") (name "unconnected-(U1-P1.15-PadZ6)") (class "Default")
      (node (ref "U1") (pin "Z6") (pinfunction "P1.15_Z6") (pintype "bidirectional"))
    )
    (net (code "71") (name "unconnected-(U2-NC1-Pad2)") (class "Default")
      (node (ref "U2") (pin "2") (pinfunction "NC1_2") (pintype "passive"))
    )
    (net (code "72") (name "unconnected-(U2-NC2-Pad5)") (class "Default")
      (node (ref "U2") (pin "5") (pinfunction "NC2_5") (pintype "passive"))
    )
  )
)
